# wb.net
KiCad netlist of a schematic drawn in EAGLE
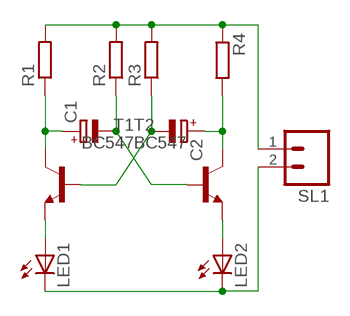
[diagram p0: schematic, sheet 1]

(export (version "E")
  (design (tool "Eeschema 10.0.6"))
  (components
    (comp (ref "C1")
      (value "CPOL-EUE2.5-7")
      (footprint "eagle-import:E2,5-7")
      (libsource (lib "eagle-import") (part "CPOL-EUE2.5-7"))
    )
    (comp (ref "C2")
      (value "CPOL-EUE2.5-7")
      (footprint "eagle-import:E2,5-7")
      (libsource (lib "eagle-import") (part "CPOL-EUE2.5-7"))
    )
    (comp (ref "LED1")
      (value "LED5MM")
      (footprint "eagle-import:LED5MM")
      (libsource (lib "eagle-import") (part "LED5MM"))
    )
    (comp (ref "LED2")
      (value "LED5MM")
      (footprint "eagle-import:LED5MM")
      (libsource (lib "eagle-import") (part "LED5MM"))
    )
    (comp (ref "R1")
      (value "R-EU_0204/5")
      (footprint "eagle-import:0204_5")
      (libsource (lib "eagle-import") (part "R-EU_0204/5"))
    )
    (comp (ref "R2")
      (value "R-EU_0204/5")
      (footprint "eagle-import:0204_5")
      (libsource (lib "eagle-import") (part "R-EU_0204/5"))
    )
    (comp (ref "R3")
      (value "R-EU_0204/5")
      (footprint "eagle-import:0204_5")
      (libsource (lib "eagle-import") (part "R-EU_0204/5"))
    )
    (comp (ref "R4")
      (value "R-EU_0204/5")
      (footprint "eagle-import:0204_5")
      (libsource (lib "eagle-import") (part "R-EU_0204/5"))
    )
    (comp (ref "SL1")
      (value "M02")
      (footprint "eagle-import:02P")
      (libsource (lib "eagle-import") (part "M02"))
    )
    (comp (ref "T1")
      (value "BC547")
      (footprint "eagle-import:TO92")
      (libsource (lib "eagle-import") (part "BC547"))
    )
    (comp (ref "T2")
      (value "BC547")
      (footprint "eagle-import:TO92")
      (libsource (lib "eagle-import") (part "BC547"))
    )
  )
  (nets
    (net (code "1") (name "Net-(LED1-C)") (class "Default")
      (node (ref "LED1") (pin "K") (pinfunction "C_K") (pintype "passive"))
      (node (ref "LED2") (pin "K") (pinfunction "C_K") (pintype "passive"))
      (node (ref "SL1") (pin "2") (pinfunction "2_2") (pintype "passive"))
    )
    (net (code "2") (name "Net-(R1-Pad2)") (class "Default")
      (node (ref "R1") (pin "2") (pinfunction "2_2") (pintype "passive"))
      (node (ref "R2") (pin "2") (pinfunction "2_2") (pintype "passive"))
      (node (ref "R3") (pin "2") (pinfunction "2_2") (pintype "passive"))
      (node (ref "R4") (pin "1") (pinfunction "1_1") (pintype "passive"))
      (node (ref "SL1") (pin "1") (pinfunction "1_1") (pintype "passive"))
    )
    (net (code "3") (name "Net-(T1-B)") (class "Default")
      (node (ref "C2") (pin "-") (pinfunction "-_-") (pintype "passive"))
      (node (ref "R3") (pin "1") (pinfunction "1_1") (pintype "passive"))
      (node (ref "T1") (pin "2") (pinfunction "B_2") (pintype "passive"))
    )
    (net (code "4") (name "Net-(T1-C)") (class "Default")
      (node (ref "C1") (pin "+") (pinfunction "+_+") (pintype "passive"))
      (node (ref "R1") (pin "1") (pinfunction "1_1") (pintype "passive"))
      (node (ref "T1") (pin "3") (pinfunction "C_3") (pintype "passive"))
    )
    (net (code "5") (name "Net-(T1-E)") (class "Default")
      (node (ref "LED1") (pin "A") (pinfunction "A_A") (pintype "passive"))
      (node (ref "T1") (pin "1") (pinfunction "E_1") (pintype "passive"))
    )
    (net (code "6") (name "Net-(T2-B)") (class "Default")
      (node (ref "C1") (pin "-") (pinfunction "-_-") (pintype "passive"))
      (node (ref "R2") (pin "1") (pinfunction "1_1") (pintype "passive"))
      (node (ref "T2") (pin "2") (pinfunction "B_2") (pintype "passive"))
    )
    (net (code "7") (name "Net-(T2-C)") (class "Default")
      (node (ref "C2") (pin "+") (pinfunction "+_+") (pintype "passive"))
      (node (ref "R4") (pin "2") (pinfunction "2_2") (pintype "passive"))
      (node (ref "T2") (pin "3") (pinfunction "C_3") (pintype "passive"))
    )
    (net (code "8") (name "Net-(T2-E)") (class "Default")
      (node (ref "LED2") (pin "A") (pinfunction "A_A") (pintype "passive"))
      (node (ref "T2") (pin "1") (pinfunction "E_1") (pintype "passive"))
    )
  )
)
